# Sheet1.net
KiCad netlist of a schematic drawn in Altium Designer
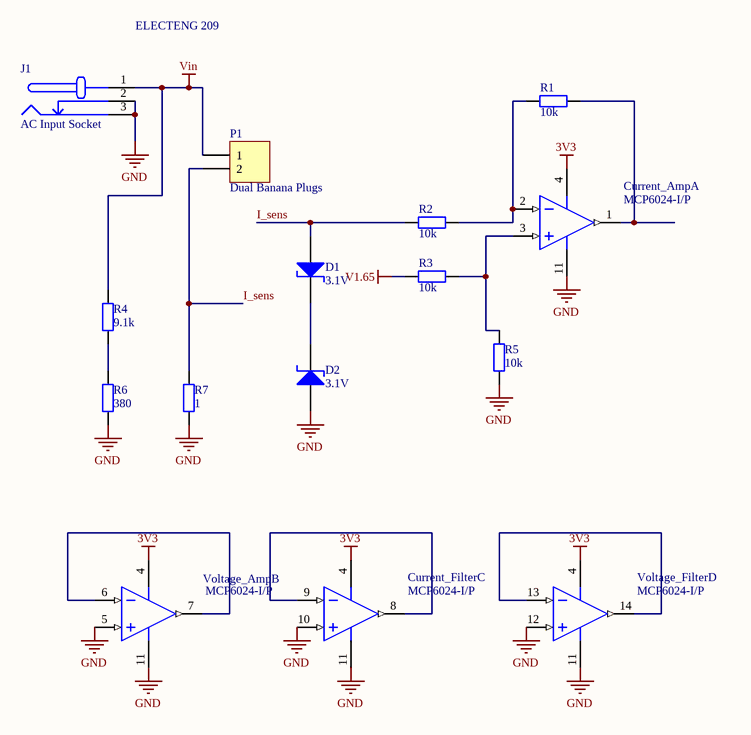
[diagram p0: Sheet1.SchDoc]

(export (version "E")
  (design (tool "Eeschema 10.0.6"))
  (components
    (comp (ref "Current_Amp")
      (value "MCP6024-I/P")
      (footprint "DIP-14")
      (description "Rail-to-Rail Input/Output, 10 MHz Operational Amplifier, 14-Pin PDIP, Industrial Temperature")
      (fields (field (name "PUBLISHER") "Altium Limited"))
      (libsource (lib "EE209_SCHLibrary") (part "MCP6024-I/P"))
    )
    (comp (ref "Current_Filter")
      (value "MCP6024-I/P")
      (footprint "DIP-14")
      (description "Rail-to-Rail Input/Output, 10 MHz Operational Amplifier, 14-Pin PDIP, Industrial Temperature")
      (fields (field (name "PUBLISHER") "Altium Limited"))
      (libsource (lib "EE209_SCHLibrary") (part "MCP6024-I/P"))
    )
    (comp (ref "D1")
      (value "3.1V")
      (footprint "AXIAL-DIODE-0.4")
      (description "Zener Diode")
      (libsource (lib "EE209_SCHLibrary") (part "Zener"))
    )
    (comp (ref "D2")
      (value "3.1V")
      (footprint "AXIAL-DIODE-0.4")
      (description "Zener Diode")
      (libsource (lib "EE209_SCHLibrary") (part "Zener"))
    )
    (comp (ref "J1")
      (value "AC Input Socket")
      (footprint "AC-Socket")
      (libsource (lib "EE209_SCHLibrary") (part "AC Input"))
    )
    (comp (ref "P1")
      (value "Dual Banana Plugs")
      (footprint "Dual Banana Plug")
      (description "M6 Holes")
      (fields (field (name "PUBLISHER") "Altium Limited"))
      (libsource (lib "EE209_SCHLibrary") (part "Dual Banana Plugs"))
    )
    (comp (ref "R1")
      (value "10k")
      (footprint "AXIAL-0.4")
      (description "Through Hole Resistor")
      (fields (field (name "PUBLISHER") "Altium Limited"))
      (libsource (lib "") (part "Res_1"))
    )
    (comp (ref "R2")
      (value "10k")
      (footprint "AXIAL-0.4")
      (description "Through Hole Resistor")
      (fields (field (name "PUBLISHER") "Altium Limited"))
      (libsource (lib "") (part "Res_1"))
    )
    (comp (ref "R3")
      (value "10k")
      (footprint "AXIAL-0.4")
      (description "Through Hole Resistor")
      (fields (field (name "PUBLISHER") "Altium Limited"))
      (libsource (lib "") (part "Res_1"))
    )
    (comp (ref "R4")
      (value "9.1k")
      (footprint "AXIAL-0.4")
      (description "Through Hole Resistor")
      (fields (field (name "PUBLISHER") "Altium Limited"))
      (libsource (lib "EE209_SCHLibrary") (part "Res"))
    )
    (comp (ref "R5")
      (value "10k")
      (footprint "AXIAL-0.4")
      (description "Through Hole Resistor")
      (fields (field (name "PUBLISHER") "Altium Limited"))
      (libsource (lib "EE209_SCHLibrary") (part "Res"))
    )
    (comp (ref "R6")
      (value "380")
      (footprint "AXIAL-0.4")
      (description "Through Hole Resistor")
      (fields (field (name "PUBLISHER") "Altium Limited"))
      (libsource (lib "EE209_SCHLibrary") (part "Res"))
    )
    (comp (ref "R7")
      (value "1")
      (footprint "AXIAL-0.4")
      (description "Through Hole Resistor")
      (fields (field (name "PUBLISHER") "Altium Limited"))
      (libsource (lib "EE209_SCHLibrary") (part "Res"))
    )
    (comp (ref "Voltage_Amp")
      (value "MCP6024-I/P")
      (footprint "DIP-14")
      (description "Rail-to-Rail Input/Output, 10 MHz Operational Amplifier, 14-Pin PDIP, Industrial Temperature")
      (fields (field (name "PUBLISHER") "Altium Limited"))
      (libsource (lib "EE209_SCHLibrary") (part "MCP6024-I/P"))
    )
    (comp (ref "Voltage_Filter")
      (value "MCP6024-I/P")
      (footprint "DIP-14")
      (description "Rail-to-Rail Input/Output, 10 MHz Operational Amplifier, 14-Pin PDIP, Industrial Temperature")
      (fields (field (name "PUBLISHER") "Altium Limited"))
      (libsource (lib "EE209_SCHLibrary") (part "MCP6024-I/P"))
    )
  )
  (nets
    (net (code "1") (name "/I_sens") (class "Default")
      (node (ref "D1") (pin "1") (pinfunction "A_1") (pintype "passive"))
      (node (ref "P1") (pin "2") (pinfunction "2_2") (pintype "passive"))
      (node (ref "R2") (pin "2") (pinfunction "2_2") (pintype "passive"))
      (node (ref "R7") (pin "2") (pinfunction "2_2") (pintype "passive"))
    )
    (net (code "2") (name "3V3") (class "Default")
      (node (ref "Current_Amp") (pin "4") (pinfunction "VDD_4") (pintype "power_in"))
      (node (ref "Current_Filter") (pin "4") (pinfunction "VDD_4") (pintype "power_in"))
      (node (ref "Voltage_Amp") (pin "4") (pinfunction "VDD_4") (pintype "power_in"))
      (node (ref "Voltage_Filter") (pin "4") (pinfunction "VDD_4") (pintype "power_in"))
    )
    (net (code "3") (name "GND") (class "Default")
      (node (ref "Current_Amp") (pin "11") (pinfunction "VSS_11") (pintype "power_in"))
      (node (ref "Current_Filter") (pin "10") (pinfunction "VINC+_10") (pintype "input"))
      (node (ref "Current_Filter") (pin "11") (pinfunction "VSS_11") (pintype "power_in"))
      (node (ref "D2") (pin "1") (pinfunction "A_1") (pintype "passive"))
      (node (ref "J1") (pin "2") (pinfunction "GND_ALT_2") (pintype "power_in"))
      (node (ref "J1") (pin "3") (pinfunction "GND_3") (pintype "power_in"))
      (node (ref "R5") (pin "1") (pinfunction "1_1") (pintype "passive"))
      (node (ref "R6") (pin "1") (pinfunction "1_1") (pintype "passive"))
      (node (ref "R7") (pin "1") (pinfunction "1_1") (pintype "passive"))
      (node (ref "Voltage_Amp") (pin "11") (pinfunction "VSS_11") (pintype "power_in"))
      (node (ref "Voltage_Amp") (pin "5") (pinfunction "VINB+_5") (pintype "input"))
      (node (ref "Voltage_Filter") (pin "11") (pinfunction "VSS_11") (pintype "power_in"))
      (node (ref "Voltage_Filter") (pin "12") (pinfunction "VIND+_12") (pintype "input"))
    )
    (net (code "4") (name "Net-(Current_AmpA-VINA+)") (class "Default")
      (node (ref "Current_Amp") (pin "3") (pinfunction "VINA+_3") (pintype "input"))
      (node (ref "R3") (pin "1") (pinfunction "1_1") (pintype "passive"))
      (node (ref "R5") (pin "2") (pinfunction "2_2") (pintype "passive"))
    )
    (net (code "5") (name "Net-(Current_AmpA-VINA-)") (class "Default")
      (node (ref "Current_Amp") (pin "2") (pinfunction "VINA-_2") (pintype "input"))
      (node (ref "R1") (pin "2") (pinfunction "2_2") (pintype "passive"))
      (node (ref "R2") (pin "1") (pinfunction "1_1") (pintype "passive"))
    )
    (net (code "6") (name "Net-(Current_AmpA-VOUTA)") (class "Default")
      (node (ref "Current_Amp") (pin "1") (pinfunction "VOUTA_1") (pintype "output"))
      (node (ref "R1") (pin "1") (pinfunction "1_1") (pintype "passive"))
    )
    (net (code "7") (name "Net-(Current_FilterC-VINC-)") (class "Default")
      (node (ref "Current_Filter") (pin "8") (pinfunction "VOUTC_8") (pintype "output"))
      (node (ref "Current_Filter") (pin "9") (pinfunction "VINC-_9") (pintype "input"))
    )
    (net (code "8") (name "Net-(D1-K)") (class "Default")
      (node (ref "D1") (pin "2") (pinfunction "K_2") (pintype "passive"))
      (node (ref "D2") (pin "2") (pinfunction "K_2") (pintype "passive"))
    )
    (net (code "9") (name "Net-(R4-Pad1)") (class "Default")
      (node (ref "R4") (pin "1") (pinfunction "1_1") (pintype "passive"))
      (node (ref "R6") (pin "2") (pinfunction "2_2") (pintype "passive"))
    )
    (net (code "10") (name "Net-(Voltage_AmpB-VINB-)") (class "Default")
      (node (ref "Voltage_Amp") (pin "6") (pinfunction "VINB-_6") (pintype "input"))
      (node (ref "Voltage_Amp") (pin "7") (pinfunction "VOUTB_7") (pintype "output"))
    )
    (net (code "11") (name "Net-(Voltage_FilterD-VIND-)") (class "Default")
      (node (ref "Voltage_Filter") (pin "13") (pinfunction "VIND-_13") (pintype "input"))
      (node (ref "Voltage_Filter") (pin "14") (pinfunction "VOUTD_14") (pintype "output"))
    )
    (net (code "12") (name "V1.65") (class "Default")
      (node (ref "R3") (pin "2") (pinfunction "2_2") (pintype "passive"))
    )
    (net (code "13") (name "Vin") (class "Default")
      (node (ref "J1") (pin "1") (pinfunction "VCC_1") (pintype "power_in"))
      (node (ref "P1") (pin "1") (pinfunction "1_1") (pintype "passive"))
      (node (ref "R4") (pin "2") (pinfunction "2_2") (pintype "passive"))
    )
  )
)
